# MAGIsDebugger-STLink.net
KiCad netlist of a schematic drawn in Altium Designer
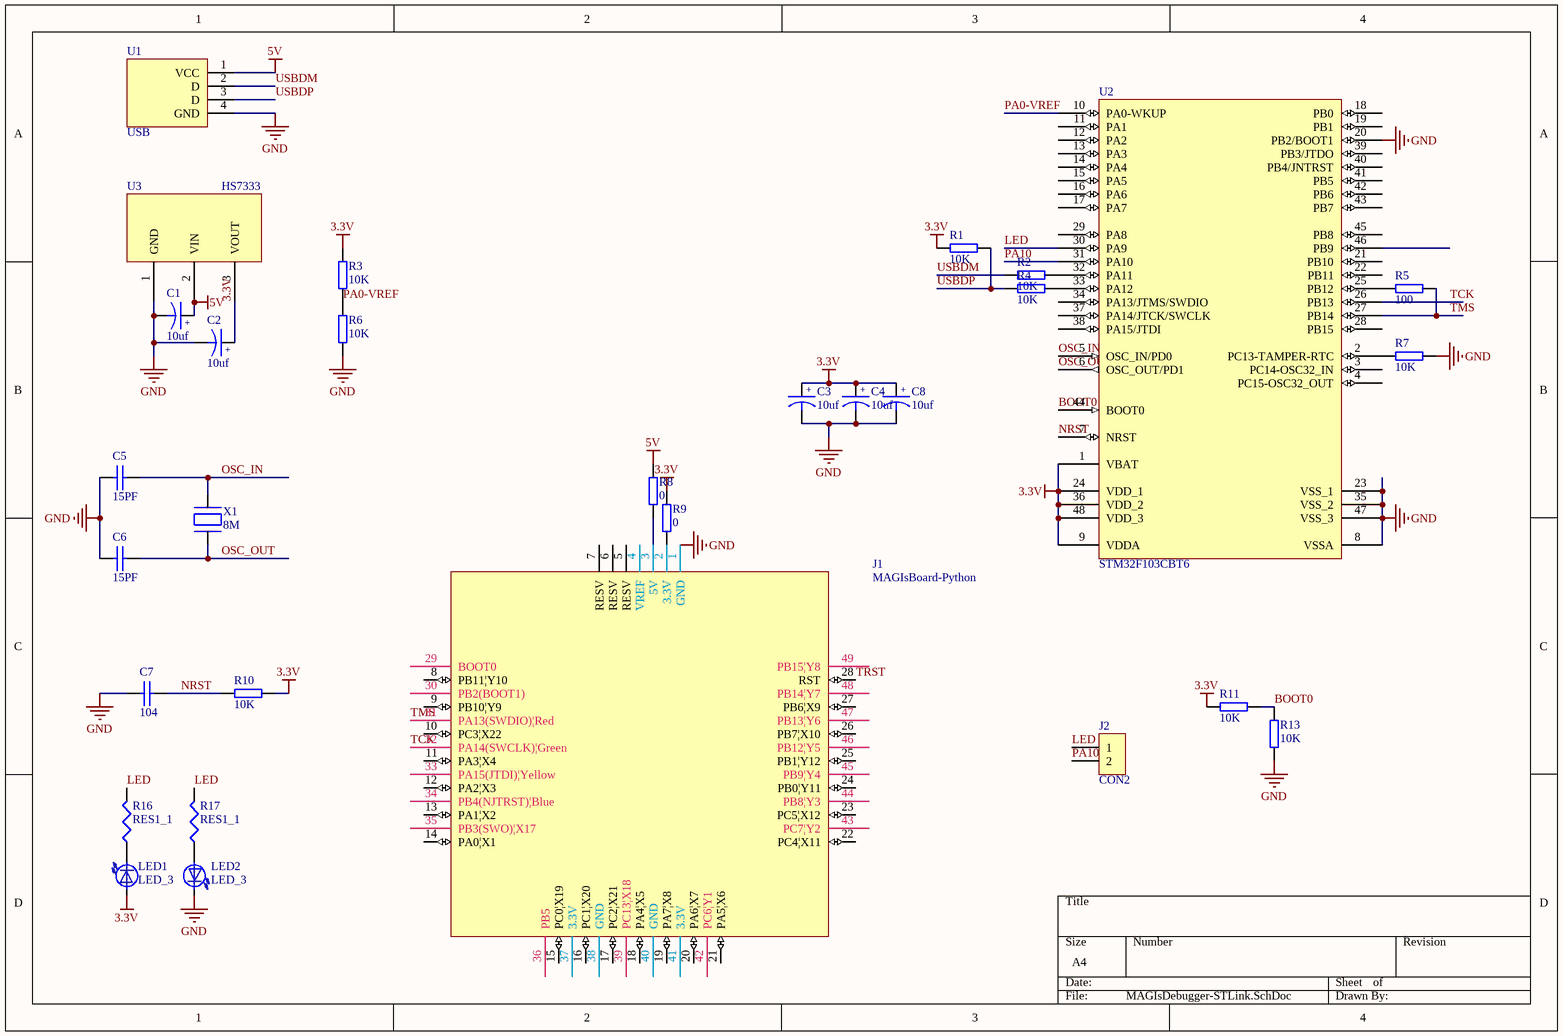
[diagram p0: MAGIsDebugger-STLink.SchDoc]

(export (version "E")
  (design (tool "Eeschema 10.0.6"))
  (components
    (comp (ref "C1")
      (value "10uf")
      (footprint "6-0805_n")
      (description "Capacitor")
      (libsource (lib "电容器") (part "CAPACITOR POL"))
    )
    (comp (ref "C2")
      (value "10uf")
      (footprint "6-0805_n")
      (description "Capacitor")
      (libsource (lib "电容器") (part "CAPACITOR POL"))
    )
    (comp (ref "C3")
      (value "10uf")
      (footprint "6-0805_n")
      (description "Capacitor")
      (libsource (lib "电容器") (part "CAPACITOR POL"))
    )
    (comp (ref "C4")
      (value "10uf")
      (footprint "6-0805_N")
      (description "Capacitor")
      (libsource (lib "电容器") (part "CAPACITOR POL"))
    )
    (comp (ref "C5") (value "15PF") (footprint "6-0805_n") (libsource (lib "STM32") (part "CAP")))
    (comp (ref "C6") (value "15PF") (footprint "6-0805_n") (libsource (lib "STM32") (part "CAP")))
    (comp (ref "C7") (value "104") (footprint "6-0805_n") (libsource (lib "STM32") (part "CAP")))
    (comp (ref "C8")
      (value "10uf")
      (footprint "6-0805_N")
      (description "Capacitor")
      (libsource (lib "电容器") (part "CAPACITOR POL"))
    )
    (comp (ref "J1")
      (value "MAGIsBoard-Python")
      (footprint "MAGIsBoard-Python")
      (libsource (lib "MAGIsBoard") (part "MAGIsBoard-Python"))
    )
    (comp (ref "J2")
      (value "CON2")
      (footprint "SIP2")
      (description "Connector")
      (libsource (lib "CON系列") (part "CON2"))
    )
    (comp (ref "LED1") (value "LED_3") (footprint "6-0805_n") (libsource (lib "二极管") (part "LED_3")))
    (comp (ref "LED2") (value "LED_3") (footprint "6-0805_n") (libsource (lib "二极管") (part "LED_3")))
    (comp (ref "R1") (value "10K") (footprint "6-0805_n") (libsource (lib "STM32") (part "RES")))
    (comp (ref "R2") (value "10K") (footprint "6-0805_n") (libsource (lib "STM32") (part "RES")))
    (comp (ref "R3") (value "10K") (footprint "6-0805_n") (libsource (lib "STM32") (part "RES")))
    (comp (ref "R4") (value "10K") (footprint "6-0805_n") (libsource (lib "STM32") (part "RES")))
    (comp (ref "R5") (value "100") (footprint "6-0805_n") (libsource (lib "STM32") (part "RES")))
    (comp (ref "R6") (value "10K") (footprint "6-0805_n") (libsource (lib "STM32") (part "RES")))
    (comp (ref "R7") (value "10K") (footprint "6-0805_n") (libsource (lib "STM32") (part "RES")))
    (comp (ref "R8") (value "0") (footprint "6-0805_n") (libsource (lib "STM32") (part "RES")))
    (comp (ref "R9") (value "0") (footprint "6-0805_n") (libsource (lib "STM32") (part "RES")))
    (comp (ref "R10") (value "10K") (footprint "6-0805_n") (libsource (lib "STM32") (part "RES")))
    (comp (ref "R11") (value "10K") (footprint "6-0805_n") (libsource (lib "STM32") (part "RES")))
    (comp (ref "R13") (value "10K") (footprint "6-0805_n") (libsource (lib "STM32") (part "RES")))
    (comp (ref "R16") (value "RES1_1") (footprint "6-0805_n") (libsource (lib "电阻器") (part "RES1_1")))
    (comp (ref "R17") (value "RES1_1") (footprint "6-0805_n") (libsource (lib "电阻器") (part "RES1_1")))
    (comp (ref "U1") (value "USB") (footprint "microUSB") (libsource (lib "USB接口") (part "USB")))
    (comp (ref "U2")
      (value "STM32F103CBT6")
      (footprint "LQFP48_N")
      (description "STM32 ARM-based 32-bit MCU with 128 Kbytes Flash, 48-pin LQFP, Industrial Temperature")
      (fields (field (name "PUBLISHER") "Altium Limited"))
      (libsource (lib "ST Microcontroller 32-Bit STM32") (part "STM32F103CBT6"))
    )
    (comp (ref "U3") (value "HS7333") (footprint "HS7333") (libsource (lib "PMIC") (part "HS7333")))
    (comp (ref "X1") (value "8M") (footprint "5032") (libsource (lib "STM32") (part "CRYSTAL")))
  )
  (nets
    (net (code "1") (name "/BOOT0") (class "Default")
      (node (ref "R11") (pin "1") (pinfunction "1_1") (pintype "passive"))
      (node (ref "R13") (pin "2") (pinfunction "2_2") (pintype "passive"))
      (node (ref "U2") (pin "44") (pinfunction "BOOT0_44") (pintype "input"))
    )
    (net (code "2") (name "/LED") (class "Default")
      (node (ref "J2") (pin "1") (pinfunction "1_1") (pintype "passive"))
      (node (ref "R16") (pin "2") (pinfunction "2_2") (pintype "passive"))
      (node (ref "R17") (pin "2") (pinfunction "2_2") (pintype "passive"))
      (node (ref "U2") (pin "30") (pinfunction "PA9_30") (pintype "bidirectional"))
    )
    (net (code "3") (name "/NRST") (class "Default")
      (node (ref "C7") (pin "2") (pinfunction "2_2") (pintype "passive"))
      (node (ref "R10") (pin "1") (pinfunction "1_1") (pintype "passive"))
      (node (ref "U2") (pin "7") (pinfunction "NRST_7") (pintype "bidirectional"))
    )
    (net (code "4") (name "/OSC_IN") (class "Default")
      (node (ref "C5") (pin "2") (pinfunction "2_2") (pintype "passive"))
      (node (ref "U2") (pin "5") (pinfunction "OSC_IN/PD0_5") (pintype "input"))
      (node (ref "X1") (pin "1") (pinfunction "1_1") (pintype "passive"))
    )
    (net (code "5") (name "/OSC_OUT") (class "Default")
      (node (ref "C6") (pin "2") (pinfunction "2_2") (pintype "passive"))
      (node (ref "U2") (pin "6") (pinfunction "OSC_OUT/PD1_6") (pintype "output"))
      (node (ref "X1") (pin "2") (pinfunction "2_2") (pintype "passive"))
    )
    (net (code "6") (name "/PA0-VREF") (class "Default")
      (node (ref "R3") (pin "1") (pinfunction "1_1") (pintype "passive"))
      (node (ref "R6") (pin "2") (pinfunction "2_2") (pintype "passive"))
      (node (ref "U2") (pin "10") (pinfunction "PA0-WKUP_10") (pintype "bidirectional"))
    )
    (net (code "7") (name "/PA10") (class "Default")
      (node (ref "J2") (pin "2") (pinfunction "2_2") (pintype "passive"))
      (node (ref "U2") (pin "31") (pinfunction "PA10_31") (pintype "bidirectional"))
    )
    (net (code "8") (name "/TCK") (class "Default")
      (node (ref "J1") (pin "32") (pinfunction "PA14(SWCLK)¦Green_32") (pintype "passive"))
      (node (ref "U2") (pin "26") (pinfunction "PB13_26") (pintype "bidirectional"))
    )
    (net (code "9") (name "/TMS") (class "Default")
      (node (ref "J1") (pin "31") (pinfunction "PA13(SWDIO)¦Red_31") (pintype "passive"))
      (node (ref "R5") (pin "1") (pinfunction "1_1") (pintype "passive"))
      (node (ref "U2") (pin "27") (pinfunction "PB14_27") (pintype "bidirectional"))
    )
    (net (code "10") (name "/TRST") (class "Default")
      (node (ref "J1") (pin "28") (pinfunction "RST_28") (pintype "bidirectional"))
    )
    (net (code "11") (name "/USBDM") (class "Default")
      (node (ref "R2") (pin "1") (pinfunction "1_1") (pintype "passive"))
      (node (ref "U1") (pin "2") (pinfunction "D_2") (pintype "passive"))
    )
    (net (code "12") (name "/USBDP") (class "Default")
      (node (ref "R1") (pin "2") (pinfunction "2_2") (pintype "passive"))
      (node (ref "R4") (pin "1") (pinfunction "1_1") (pintype "passive"))
      (node (ref "U1") (pin "3") (pinfunction "D_3") (pintype "passive"))
    )
    (net (code "13") (name "3.3V") (class "Default")
      (node (ref "C2") (pin "1") (pinfunction "1_1") (pintype "passive"))
      (node (ref "C3") (pin "1") (pinfunction "1_1") (pintype "passive"))
      (node (ref "C4") (pin "1") (pinfunction "1_1") (pintype "passive"))
      (node (ref "C8") (pin "1") (pinfunction "1_1") (pintype "passive"))
      (node (ref "LED1") (pin "1") (pinfunction "A_1") (pintype "passive"))
      (node (ref "R1") (pin "1") (pinfunction "1_1") (pintype "passive"))
      (node (ref "R10") (pin "2") (pinfunction "2_2") (pintype "passive"))
      (node (ref "R11") (pin "2") (pinfunction "2_2") (pintype "passive"))
      (node (ref "R3") (pin "2") (pinfunction "2_2") (pintype "passive"))
      (node (ref "R9") (pin "1") (pinfunction "1_1") (pintype "passive"))
      (node (ref "U2") (pin "1") (pinfunction "VBAT_1") (pintype "power_in"))
      (node (ref "U2") (pin "24") (pinfunction "VDD_1_24") (pintype "power_in"))
      (node (ref "U2") (pin "36") (pinfunction "VDD_2_36") (pintype "power_in"))
      (node (ref "U2") (pin "48") (pinfunction "VDD_3_48") (pintype "power_in"))
      (node (ref "U2") (pin "9") (pinfunction "VDDA_9") (pintype "power_in"))
      (node (ref "U3") (pin "3") (pinfunction "VOUT_3") (pintype "passive"))
    )
    (net (code "14") (name "5V") (class "Default")
      (node (ref "C1") (pin "1") (pinfunction "1_1") (pintype "passive"))
      (node (ref "R8") (pin "1") (pinfunction "1_1") (pintype "passive"))
      (node (ref "U1") (pin "1") (pinfunction "VCC_1") (pintype "passive"))
      (node (ref "U3") (pin "2") (pinfunction "VIN_2") (pintype "passive"))
    )
    (net (code "15") (name "GND") (class "Default")
      (node (ref "C1") (pin "2") (pinfunction "2_2") (pintype "passive"))
      (node (ref "C2") (pin "2") (pinfunction "2_2") (pintype "passive"))
      (node (ref "C3") (pin "2") (pinfunction "2_2") (pintype "passive"))
      (node (ref "C4") (pin "2") (pinfunction "2_2") (pintype "passive"))
      (node (ref "C5") (pin "1") (pinfunction "1_1") (pintype "passive"))
      (node (ref "C6") (pin "1") (pinfunction "1_1") (pintype "passive"))
      (node (ref "C7") (pin "1") (pinfunction "1_1") (pintype "passive"))
      (node (ref "C8") (pin "2") (pinfunction "2_2") (pintype "passive"))
      (node (ref "J1") (pin "1") (pinfunction "GND_1") (pintype "power_in"))
      (node (ref "LED2") (pin "2") (pinfunction "K_2") (pintype "passive"))
      (node (ref "R13") (pin "1") (pinfunction "1_1") (pintype "passive"))
      (node (ref "R6") (pin "1") (pinfunction "1_1") (pintype "passive"))
      (node (ref "R7") (pin "1") (pinfunction "1_1") (pintype "passive"))
      (node (ref "U1") (pin "4") (pinfunction "GND_4") (pintype "passive"))
      (node (ref "U2") (pin "20") (pinfunction "PB2/BOOT1_20") (pintype "bidirectional"))
      (node (ref "U2") (pin "23") (pinfunction "VSS_1_23") (pintype "power_in"))
      (node (ref "U2") (pin "35") (pinfunction "VSS_2_35") (pintype "power_in"))
      (node (ref "U2") (pin "47") (pinfunction "VSS_3_47") (pintype "power_in"))
      (node (ref "U2") (pin "8") (pinfunction "VSSA_8") (pintype "power_in"))
      (node (ref "U3") (pin "1") (pinfunction "GND_1") (pintype "passive"))
    )
    (net (code "16") (name "Net-(J1-3.3V-Pad2)") (class "Default")
      (node (ref "J1") (pin "2") (pinfunction "3.3V_2") (pintype "power_in"))
      (node (ref "R9") (pin "2") (pinfunction "2_2") (pintype "passive"))
    )
    (net (code "17") (name "Net-(J1-5V)") (class "Default")
      (node (ref "J1") (pin "3") (pinfunction "5V_3") (pintype "power_in"))
      (node (ref "R8") (pin "2") (pinfunction "2_2") (pintype "passive"))
    )
    (net (code "18") (name "Net-(LED1-K)") (class "Default")
      (node (ref "LED1") (pin "2") (pinfunction "K_2") (pintype "passive"))
      (node (ref "R16") (pin "1") (pinfunction "1_1") (pintype "passive"))
    )
    (net (code "19") (name "Net-(LED2-A)") (class "Default")
      (node (ref "LED2") (pin "1") (pinfunction "A_1") (pintype "passive"))
      (node (ref "R17") (pin "1") (pinfunction "1_1") (pintype "passive"))
    )
    (net (code "20") (name "Net-(U2-PA11)") (class "Default")
      (node (ref "R2") (pin "2") (pinfunction "2_2") (pintype "passive"))
      (node (ref "U2") (pin "32") (pinfunction "PA11_32") (pintype "bidirectional"))
    )
    (net (code "21") (name "Net-(U2-PA12)") (class "Default")
      (node (ref "R4") (pin "2") (pinfunction "2_2") (pintype "passive"))
      (node (ref "U2") (pin "33") (pinfunction "PA12_33") (pintype "bidirectional"))
    )
    (net (code "22") (name "Net-(U2-PB12)") (class "Default")
      (node (ref "R5") (pin "2") (pinfunction "2_2") (pintype "passive"))
      (node (ref "U2") (pin "25") (pinfunction "PB12_25") (pintype "bidirectional"))
    )
    (net (code "23") (name "Net-(U2-PC13-TAMPER-RTC)") (class "Default")
      (node (ref "R7") (pin "2") (pinfunction "2_2") (pintype "passive"))
      (node (ref "U2") (pin "2") (pinfunction "PC13-TAMPER-RTC_2") (pintype "bidirectional"))
    )
    (net (code "24") (name "unconnected-(J1-3.3V-Pad37)") (class "Default")
      (node (ref "J1") (pin "37") (pinfunction "3.3V_37") (pintype "passive"))
    )
    (net (code "25") (name "unconnected-(J1-3.3V-Pad41)") (class "Default")
      (node (ref "J1") (pin "41") (pinfunction "3.3V_41") (pintype "passive"))
    )
    (net (code "26") (name "unconnected-(J1-BOOT0-Pad29)") (class "Default")
      (node (ref "J1") (pin "29") (pinfunction "BOOT0_29") (pintype "passive"))
    )
    (net (code "27") (name "unconnected-(J1-GND-Pad38)") (class "Default")
      (node (ref "J1") (pin "38") (pinfunction "GND_38") (pintype "passive"))
    )
    (net (code "28") (name "unconnected-(J1-GND-Pad40)") (class "Default")
      (node (ref "J1") (pin "40") (pinfunction "GND_40") (pintype "passive"))
    )
    (net (code "29") (name "unconnected-(J1-PA0¦X1-Pad14)") (class "Default")
      (node (ref "J1") (pin "14") (pinfunction "PA0¦X1_14") (pintype "bidirectional"))
    )
    (net (code "30") (name "unconnected-(J1-PA1¦X2-Pad13)") (class "Default")
      (node (ref "J1") (pin "13") (pinfunction "PA1¦X2_13") (pintype "bidirectional"))
    )
    (net (code "31") (name "unconnected-(J1-PA2¦X3-Pad12)") (class "Default")
      (node (ref "J1") (pin "12") (pinfunction "PA2¦X3_12") (pintype "bidirectional"))
    )
    (net (code "32") (name "unconnected-(J1-PA3¦X4-Pad11)") (class "Default")
      (node (ref "J1") (pin "11") (pinfunction "PA3¦X4_11") (pintype "bidirectional"))
    )
    (net (code "33") (name "unconnected-(J1-PA4¦X5-Pad18)") (class "Default")
      (node (ref "J1") (pin "18") (pinfunction "PA4¦X5_18") (pintype "bidirectional"))
    )
    (net (code "34") (name "unconnected-(J1-PA5¦X6-Pad21)") (class "Default")
      (node (ref "J1") (pin "21") (pinfunction "PA5¦X6_21") (pintype "bidirectional"))
    )
    (net (code "35") (name "unconnected-(J1-PA6¦X7-Pad20)") (class "Default")
      (node (ref "J1") (pin "20") (pinfunction "PA6¦X7_20") (pintype "bidirectional"))
    )
    (net (code "36") (name "unconnected-(J1-PA7¦X8-Pad19)") (class "Default")
      (node (ref "J1") (pin "19") (pinfunction "PA7¦X8_19") (pintype "bidirectional"))
    )
    (net (code "37") (name "unconnected-(J1-PA15(JTDI)¦Yellow-Pad33)") (class "Default")
      (node (ref "J1") (pin "33") (pinfunction "PA15(JTDI)¦Yellow_33") (pintype "passive"))
    )
    (net (code "38") (name "unconnected-(J1-PB0¦Y11-Pad24)") (class "Default")
      (node (ref "J1") (pin "24") (pinfunction "PB0¦Y11_24") (pintype "bidirectional"))
    )
    (net (code "39") (name "unconnected-(J1-PB1¦Y12-Pad25)") (class "Default")
      (node (ref "J1") (pin "25") (pinfunction "PB1¦Y12_25") (pintype "bidirectional"))
    )
    (net (code "40") (name "unconnected-(J1-PB2(BOOT1)-Pad30)") (class "Default")
      (node (ref "J1") (pin "30") (pinfunction "PB2(BOOT1)_30") (pintype "passive"))
    )
    (net (code "41") (name "unconnected-(J1-PB3(SWO)¦X17-Pad35)") (class "Default")
      (node (ref "J1") (pin "35") (pinfunction "PB3(SWO)¦X17_35") (pintype "passive"))
    )
    (net (code "42") (name "unconnected-(J1-PB4(NJTRST)¦Blue-Pad34)") (class "Default")
      (node (ref "J1") (pin "34") (pinfunction "PB4(NJTRST)¦Blue_34") (pintype "passive"))
    )
    (net (code "43") (name "unconnected-(J1-PB5-Pad36)") (class "Default")
      (node (ref "J1") (pin "36") (pinfunction "PB5_36") (pintype "passive"))
    )
    (net (code "44") (name "unconnected-(J1-PB6¦X9-Pad27)") (class "Default")
      (node (ref "J1") (pin "27") (pinfunction "PB6¦X9_27") (pintype "bidirectional"))
    )
    (net (code "45") (name "unconnected-(J1-PB7¦X10-Pad26)") (class "Default")
      (node (ref "J1") (pin "26") (pinfunction "PB7¦X10_26") (pintype "bidirectional"))
    )
    (net (code "46") (name "unconnected-(J1-PB8¦Y3-Pad44)") (class "Default")
      (node (ref "J1") (pin "44") (pinfunction "PB8¦Y3_44") (pintype "passive"))
    )
    (net (code "47") (name "unconnected-(J1-PB9¦Y4-Pad45)") (class "Default")
      (node (ref "J1") (pin "45") (pinfunction "PB9¦Y4_45") (pintype "passive"))
    )
    (net (code "48") (name "unconnected-(J1-PB10¦Y9-Pad9)") (class "Default")
      (node (ref "J1") (pin "9") (pinfunction "PB10¦Y9_9") (pintype "bidirectional"))
    )
    (net (code "49") (name "unconnected-(J1-PB11¦Y10-Pad8)") (class "Default")
      (node (ref "J1") (pin "8") (pinfunction "PB11¦Y10_8") (pintype "bidirectional"))
    )
    (net (code "50") (name "unconnected-(J1-PB12¦Y5-Pad46)") (class "Default")
      (node (ref "J1") (pin "46") (pinfunction "PB12¦Y5_46") (pintype "passive"))
    )
    (net (code "51") (name "unconnected-(J1-PB13¦Y6-Pad47)") (class "Default")
      (node (ref "J1") (pin "47") (pinfunction "PB13¦Y6_47") (pintype "passive"))
    )
    (net (code "52") (name "unconnected-(J1-PB14¦Y7-Pad48)") (class "Default")
      (node (ref "J1") (pin "48") (pinfunction "PB14¦Y7_48") (pintype "passive"))
    )
    (net (code "53") (name "unconnected-(J1-PB15¦Y8-Pad49)") (class "Default")
      (node (ref "J1") (pin "49") (pinfunction "PB15¦Y8_49") (pintype "passive"))
    )
    (net (code "54") (name "unconnected-(J1-PC0¦X19-Pad15)") (class "Default")
      (node (ref "J1") (pin "15") (pinfunction "PC0¦X19_15") (pintype "bidirectional"))
    )
    (net (code "55") (name "unconnected-(J1-PC1¦X20-Pad16)") (class "Default")
      (node (ref "J1") (pin "16") (pinfunction "PC1¦X20_16") (pintype "bidirectional"))
    )
    (net (code "56") (name "unconnected-(J1-PC2¦X21-Pad17)") (class "Default")
      (node (ref "J1") (pin "17") (pinfunction "PC2¦X21_17") (pintype "bidirectional"))
    )
    (net (code "57") (name "unconnected-(J1-PC3¦X22-Pad10)") (class "Default")
      (node (ref "J1") (pin "10") (pinfunction "PC3¦X22_10") (pintype "bidirectional"))
    )
    (net (code "58") (name "unconnected-(J1-PC4¦X11-Pad22)") (class "Default")
      (node (ref "J1") (pin "22") (pinfunction "PC4¦X11_22") (pintype "bidirectional"))
    )
    (net (code "59") (name "unconnected-(J1-PC5¦X12-Pad23)") (class "Default")
      (node (ref "J1") (pin "23") (pinfunction "PC5¦X12_23") (pintype "bidirectional"))
    )
    (net (code "60") (name "unconnected-(J1-PC6¦Y1-Pad42)") (class "Default")
      (node (ref "J1") (pin "42") (pinfunction "PC6¦Y1_42") (pintype "passive"))
    )
    (net (code "61") (name "unconnected-(J1-PC7¦Y2-Pad43)") (class "Default")
      (node (ref "J1") (pin "43") (pinfunction "PC7¦Y2_43") (pintype "passive"))
    )
    (net (code "62") (name "unconnected-(J1-PC13¦X18-Pad39)") (class "Default")
      (node (ref "J1") (pin "39") (pinfunction "PC13¦X18_39") (pintype "passive"))
    )
    (net (code "63") (name "unconnected-(J1-RESV-Pad5)") (class "Default")
      (node (ref "J1") (pin "5") (pinfunction "RESV_5") (pintype "passive"))
    )
    (net (code "64") (name "unconnected-(J1-RESV-Pad6)") (class "Default")
      (node (ref "J1") (pin "6") (pinfunction "RESV_6") (pintype "passive"))
    )
    (net (code "65") (name "unconnected-(J1-RESV-Pad7)") (class "Default")
      (node (ref "J1") (pin "7") (pinfunction "RESV_7") (pintype "passive"))
    )
    (net (code "66") (name "unconnected-(J1-VREF-Pad4)") (class "Default")
      (node (ref "J1") (pin "4") (pinfunction "VREF_4") (pintype "passive"))
    )
    (net (code "67") (name "unconnected-(U2-PA1-Pad11)") (class "Default")
      (node (ref "U2") (pin "11") (pinfunction "PA1_11") (pintype "bidirectional"))
    )
    (net (code "68") (name "unconnected-(U2-PA2-Pad12)") (class "Default")
      (node (ref "U2") (pin "12") (pinfunction "PA2_12") (pintype "bidirectional"))
    )
    (net (code "69") (name "unconnected-(U2-PA3-Pad13)") (class "Default")
      (node (ref "U2") (pin "13") (pinfunction "PA3_13") (pintype "bidirectional"))
    )
    (net (code "70") (name "unconnected-(U2-PA4-Pad14)") (class "Default")
      (node (ref "U2") (pin "14") (pinfunction "PA4_14") (pintype "bidirectional"))
    )
    (net (code "71") (name "unconnected-(U2-PA5-Pad15)") (class "Default")
      (node (ref "U2") (pin "15") (pinfunction "PA5_15") (pintype "bidirectional"))
    )
    (net (code "72") (name "unconnected-(U2-PA6-Pad16)") (class "Default")
      (node (ref "U2") (pin "16") (pinfunction "PA6_16") (pintype "bidirectional"))
    )
    (net (code "73") (name "unconnected-(U2-PA7-Pad17)") (class "Default")
      (node (ref "U2") (pin "17") (pinfunction "PA7_17") (pintype "bidirectional"))
    )
    (net (code "74") (name "unconnected-(U2-PA8-Pad29)") (class "Default")
      (node (ref "U2") (pin "29") (pinfunction "PA8_29") (pintype "bidirectional"))
    )
    (net (code "75") (name "unconnected-(U2-PA13{slash}JTMS{slash}SWDIO-Pad34)") (class "Default")
      (node (ref "U2") (pin "34") (pinfunction "PA13/JTMS/SWDIO_34") (pintype "bidirectional"))
    )
    (net (code "76") (name "unconnected-(U2-PA14{slash}JTCK{slash}SWCLK-Pad37)") (class "Default")
      (node (ref "U2") (pin "37") (pinfunction "PA14/JTCK/SWCLK_37") (pintype "bidirectional"))
    )
    (net (code "77") (name "unconnected-(U2-PA15{slash}JTDI-Pad38)") (class "Default")
      (node (ref "U2") (pin "38") (pinfunction "PA15/JTDI_38") (pintype "bidirectional"))
    )
    (net (code "78") (name "unconnected-(U2-PB0-Pad18)") (class "Default")
      (node (ref "U2") (pin "18") (pinfunction "PB0_18") (pintype "bidirectional"))
    )
    (net (code "79") (name "unconnected-(U2-PB1-Pad19)") (class "Default")
      (node (ref "U2") (pin "19") (pinfunction "PB1_19") (pintype "bidirectional"))
    )
    (net (code "80") (name "unconnected-(U2-PB3{slash}JTDO-Pad39)") (class "Default")
      (node (ref "U2") (pin "39") (pinfunction "PB3/JTDO_39") (pintype "bidirectional"))
    )
    (net (code "81") (name "unconnected-(U2-PB4{slash}JNTRST-Pad40)") (class "Default")
      (node (ref "U2") (pin "40") (pinfunction "PB4/JNTRST_40") (pintype "bidirectional"))
    )
    (net (code "82") (name "unconnected-(U2-PB5-Pad41)") (class "Default")
      (node (ref "U2") (pin "41") (pinfunction "PB5_41") (pintype "bidirectional"))
    )
    (net (code "83") (name "unconnected-(U2-PB6-Pad42)") (class "Default")
      (node (ref "U2") (pin "42") (pinfunction "PB6_42") (pintype "bidirectional"))
    )
    (net (code "84") (name "unconnected-(U2-PB7-Pad43)") (class "Default")
      (node (ref "U2") (pin "43") (pinfunction "PB7_43") (pintype "bidirectional"))
    )
    (net (code "85") (name "unconnected-(U2-PB8-Pad45)") (class "Default")
      (node (ref "U2") (pin "45") (pinfunction "PB8_45") (pintype "bidirectional"))
    )
    (net (code "86") (name "unconnected-(U2-PB9-Pad46)") (class "Default")
      (node (ref "U2") (pin "46") (pinfunction "PB9_46") (pintype "bidirectional"))
    )
    (net (code "87") (name "unconnected-(U2-PB10-Pad21)") (class "Default")
      (node (ref "U2") (pin "21") (pinfunction "PB10_21") (pintype "bidirectional"))
    )
    (net (code "88") (name "unconnected-(U2-PB11-Pad22)") (class "Default")
      (node (ref "U2") (pin "22") (pinfunction "PB11_22") (pintype "bidirectional"))
    )
    (net (code "89") (name "unconnected-(U2-PB15-Pad28)") (class "Default")
      (node (ref "U2") (pin "28") (pinfunction "PB15_28") (pintype "bidirectional"))
    )
    (net (code "90") (name "unconnected-(U2-PC14-OSC32_IN-Pad3)") (class "Default")
      (node (ref "U2") (pin "3") (pinfunction "PC14-OSC32_IN_3") (pintype "bidirectional"))
    )
    (net (code "91") (name "unconnected-(U2-PC15-OSC32_OUT-Pad4)") (class "Default")
      (node (ref "U2") (pin "4") (pinfunction "PC15-OSC32_OUT_4") (pintype "bidirectional"))
    )
  )
)
